# LED_CONV_SIG.net
KiCad netlist of a schematic drawn in Altium Designer
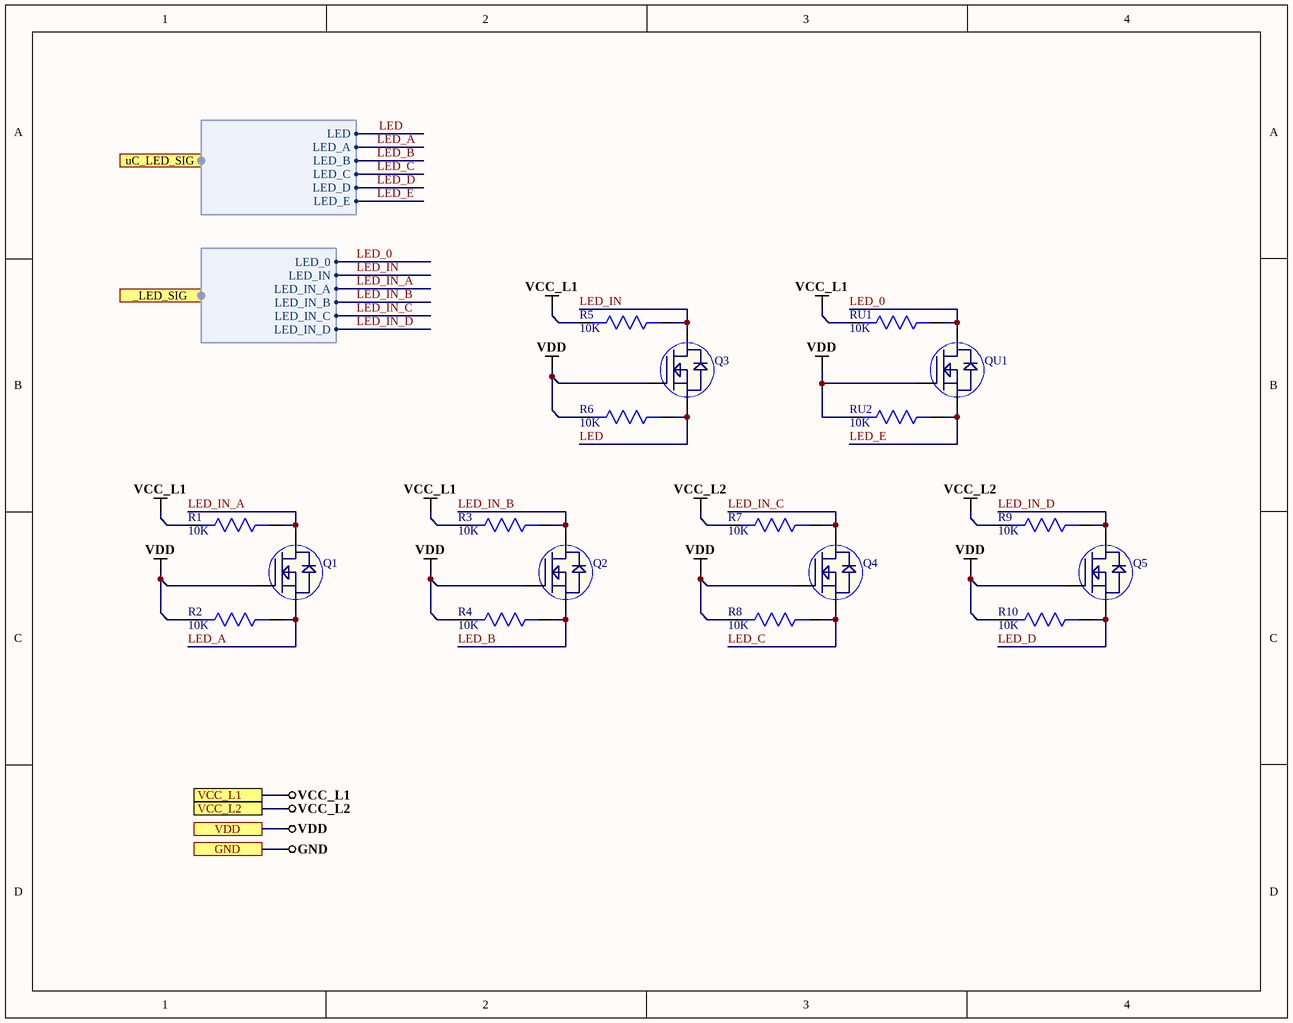
[diagram p0: LED_CONV_SIG.SchDoc]

(export (version "E")
  (design (tool "Eeschema 10.0.6"))
  (components
    (comp (ref "Q1")
      (value "BSS138LT1G")
      (footprint "SOT23-3")
      (description "MOSFET N-CH 50V 200MA SOT-23")
      (fields (field (name "MANUFACTURER") "ON Semiconductor"))
      (libsource (lib "TT_IntLib") (part "BSS138LT1G"))
    )
    (comp (ref "Q2")
      (value "BSS138LT1G")
      (footprint "SOT23-3")
      (description "MOSFET N-CH 50V 200MA SOT-23")
      (fields (field (name "MANUFACTURER") "ON Semiconductor"))
      (libsource (lib "TT_IntLib") (part "BSS138LT1G"))
    )
    (comp (ref "Q3")
      (value "BSS138LT1G")
      (footprint "SOT23-3")
      (description "MOSFET N-CH 50V 200MA SOT-23")
      (fields (field (name "MANUFACTURER") "ON Semiconductor"))
      (libsource (lib "TT_IntLib") (part "BSS138LT1G"))
    )
    (comp (ref "Q4")
      (value "BSS138LT1G")
      (footprint "SOT23-3")
      (description "MOSFET N-CH 50V 200MA SOT-23")
      (fields (field (name "MANUFACTURER") "ON Semiconductor"))
      (libsource (lib "TT_IntLib") (part "BSS138LT1G"))
    )
    (comp (ref "Q5")
      (value "BSS138LT1G")
      (footprint "SOT23-3")
      (description "MOSFET N-CH 50V 200MA SOT-23")
      (fields (field (name "MANUFACTURER") "ON Semiconductor"))
      (libsource (lib "TT_IntLib") (part "BSS138LT1G"))
    )
    (comp (ref "QU1")
      (value "BSS138LT1G")
      (footprint "SOT23-3")
      (description "MOSFET N-CH 50V 200MA SOT-23")
      (fields (field (name "MANUFACTURER") "ON Semiconductor"))
      (libsource (lib "TT_IntLib") (part "BSS138LT1G"))
    )
    (comp (ref "R1")
      (value "10K")
      (footprint "Res-0201")
      (description "GENERAL 0201 11% REEL (7INCH)")
      (fields
        (field (name "MANUFACTURER") "Yageo")
        (field (name "MANUFACTURER PART NUMBER") "RC0201FR-0710KL")
      )
      (libsource (lib "TT_IntLib") (part "RC0201FR-0710KL"))
    )
    (comp (ref "R2")
      (value "10K")
      (footprint "Res-0201")
      (description "GENERAL 0201 11% REEL (7INCH)")
      (fields
        (field (name "MANUFACTURER") "Yageo")
        (field (name "MANUFACTURER PART NUMBER") "RC0201FR-0710KL")
      )
      (libsource (lib "TT_IntLib") (part "RC0201FR-0710KL"))
    )
    (comp (ref "R3")
      (value "10K")
      (footprint "Res-0201")
      (description "GENERAL 0201 11% REEL (7INCH)")
      (fields
        (field (name "MANUFACTURER") "Yageo")
        (field (name "MANUFACTURER PART NUMBER") "RC0201FR-0710KL")
      )
      (libsource (lib "TT_IntLib") (part "RC0201FR-0710KL"))
    )
    (comp (ref "R4")
      (value "10K")
      (footprint "Res-0201")
      (description "GENERAL 0201 11% REEL (7INCH)")
      (fields
        (field (name "MANUFACTURER") "Yageo")
        (field (name "MANUFACTURER PART NUMBER") "RC0201FR-0710KL")
      )
      (libsource (lib "TT_IntLib") (part "RC0201FR-0710KL"))
    )
    (comp (ref "R5")
      (value "10K")
      (footprint "Res-0201")
      (description "GENERAL 0201 11% REEL (7INCH)")
      (fields
        (field (name "MANUFACTURER") "Yageo")
        (field (name "MANUFACTURER PART NUMBER") "RC0201FR-0710KL")
      )
      (libsource (lib "TT_IntLib") (part "RC0201FR-0710KL"))
    )
    (comp (ref "R6")
      (value "10K")
      (footprint "Res-0201")
      (description "GENERAL 0201 11% REEL (7INCH)")
      (fields
        (field (name "MANUFACTURER") "Yageo")
        (field (name "MANUFACTURER PART NUMBER") "RC0201FR-0710KL")
      )
      (libsource (lib "TT_IntLib") (part "RC0201FR-0710KL"))
    )
    (comp (ref "R7")
      (value "10K")
      (footprint "Res-0201")
      (description "GENERAL 0201 11% REEL (7INCH)")
      (fields
        (field (name "MANUFACTURER") "Yageo")
        (field (name "MANUFACTURER PART NUMBER") "RC0201FR-0710KL")
      )
      (libsource (lib "TT_IntLib") (part "RC0201FR-0710KL"))
    )
    (comp (ref "R8")
      (value "10K")
      (footprint "Res-0201")
      (description "GENERAL 0201 11% REEL (7INCH)")
      (fields
        (field (name "MANUFACTURER") "Yageo")
        (field (name "MANUFACTURER PART NUMBER") "RC0201FR-0710KL")
      )
      (libsource (lib "TT_IntLib") (part "RC0201FR-0710KL"))
    )
    (comp (ref "R9")
      (value "10K")
      (footprint "Res-0201")
      (description "GENERAL 0201 11% REEL (7INCH)")
      (fields
        (field (name "MANUFACTURER") "Yageo")
        (field (name "MANUFACTURER PART NUMBER") "RC0201FR-0710KL")
      )
      (libsource (lib "TT_IntLib") (part "RC0201FR-0710KL"))
    )
    (comp (ref "R10")
      (value "10K")
      (footprint "Res-0201")
      (description "GENERAL 0201 11% REEL (7INCH)")
      (fields
        (field (name "MANUFACTURER") "Yageo")
        (field (name "MANUFACTURER PART NUMBER") "RC0201FR-0710KL")
      )
      (libsource (lib "TT_IntLib") (part "RC0201FR-0710KL"))
    )
    (comp (ref "RU1")
      (value "10K")
      (footprint "Res-0201")
      (description "GENERAL 0201 11% REEL (7INCH)")
      (fields
        (field (name "MANUFACTURER") "Yageo")
        (field (name "MANUFACTURER PART NUMBER") "RC0201FR-0710KL")
      )
      (libsource (lib "TT_IntLib") (part "RC0201FR-0710KL"))
    )
    (comp (ref "RU2")
      (value "10K")
      (footprint "Res-0201")
      (description "GENERAL 0201 11% REEL (7INCH)")
      (fields
        (field (name "MANUFACTURER") "Yageo")
        (field (name "MANUFACTURER PART NUMBER") "RC0201FR-0710KL")
      )
      (libsource (lib "TT_IntLib") (part "RC0201FR-0710KL"))
    )
  )
  (nets
    (net (code "3") (name "/LED") (class "Default")
      (node (ref "Q3") (pin "2") (pinfunction "S_2") (pintype "passive"))
      (node (ref "R6") (pin "2") (pintype "passive"))
    )
    (net (code "4") (name "/LED_0") (class "Default")
      (node (ref "QU1") (pin "3") (pinfunction "D_3") (pintype "passive"))
      (node (ref "RU1") (pin "2") (pintype "passive"))
    )
    (net (code "5") (name "/LED_A") (class "Default")
      (node (ref "Q1") (pin "2") (pinfunction "S_2") (pintype "passive"))
      (node (ref "R2") (pin "2") (pintype "passive"))
    )
    (net (code "6") (name "/LED_B") (class "Default")
      (node (ref "Q2") (pin "2") (pinfunction "S_2") (pintype "passive"))
      (node (ref "R4") (pin "2") (pintype "passive"))
    )
    (net (code "7") (name "/LED_C") (class "Default")
      (node (ref "Q4") (pin "2") (pinfunction "S_2") (pintype "passive"))
      (node (ref "R8") (pin "2") (pintype "passive"))
    )
    (net (code "8") (name "/LED_D") (class "Default")
      (node (ref "Q5") (pin "2") (pinfunction "S_2") (pintype "passive"))
      (node (ref "R10") (pin "2") (pintype "passive"))
    )
    (net (code "9") (name "/LED_E") (class "Default")
      (node (ref "QU1") (pin "2") (pinfunction "S_2") (pintype "passive"))
      (node (ref "RU2") (pin "2") (pintype "passive"))
    )
    (net (code "10") (name "/LED_IN") (class "Default")
      (node (ref "Q3") (pin "3") (pinfunction "D_3") (pintype "passive"))
      (node (ref "R5") (pin "2") (pintype "passive"))
    )
    (net (code "11") (name "/LED_IN_A") (class "Default")
      (node (ref "Q1") (pin "3") (pinfunction "D_3") (pintype "passive"))
      (node (ref "R1") (pin "2") (pintype "passive"))
    )
    (net (code "12") (name "/LED_IN_B") (class "Default")
      (node (ref "Q2") (pin "3") (pinfunction "D_3") (pintype "passive"))
      (node (ref "R3") (pin "2") (pintype "passive"))
    )
    (net (code "13") (name "/LED_IN_C") (class "Default")
      (node (ref "Q4") (pin "3") (pinfunction "D_3") (pintype "passive"))
      (node (ref "R7") (pin "2") (pintype "passive"))
    )
    (net (code "14") (name "/LED_IN_D") (class "Default")
      (node (ref "Q5") (pin "3") (pinfunction "D_3") (pintype "passive"))
      (node (ref "R9") (pin "2") (pintype "passive"))
    )
    (net (code "18") (name "VCC_L1") (class "Default")
      (node (ref "R1") (pin "1") (pintype "passive"))
      (node (ref "R3") (pin "1") (pintype "passive"))
      (node (ref "R5") (pin "1") (pintype "passive"))
      (node (ref "RU1") (pin "1") (pintype "passive"))
    )
    (net (code "19") (name "VCC_L2") (class "Default")
      (node (ref "R7") (pin "1") (pintype "passive"))
      (node (ref "R9") (pin "1") (pintype "passive"))
    )
    (net (code "20") (name "VDD") (class "Default")
      (node (ref "Q1") (pin "1") (pinfunction "G_1") (pintype "passive"))
      (node (ref "Q2") (pin "1") (pinfunction "G_1") (pintype "passive"))
      (node (ref "Q3") (pin "1") (pinfunction "G_1") (pintype "passive"))
      (node (ref "Q4") (pin "1") (pinfunction "G_1") (pintype "passive"))
      (node (ref "Q5") (pin "1") (pinfunction "G_1") (pintype "passive"))
      (node (ref "QU1") (pin "1") (pinfunction "G_1") (pintype "passive"))
      (node (ref "R10") (pin "1") (pintype "passive"))
      (node (ref "R2") (pin "1") (pintype "passive"))
      (node (ref "R4") (pin "1") (pintype "passive"))
      (node (ref "R6") (pin "1") (pintype "passive"))
      (node (ref "R8") (pin "1") (pintype "passive"))
      (node (ref "RU2") (pin "1") (pintype "passive"))
    )
  )
)
